# GPSModule.net
KiCad netlist of a schematic drawn in Altium Designer
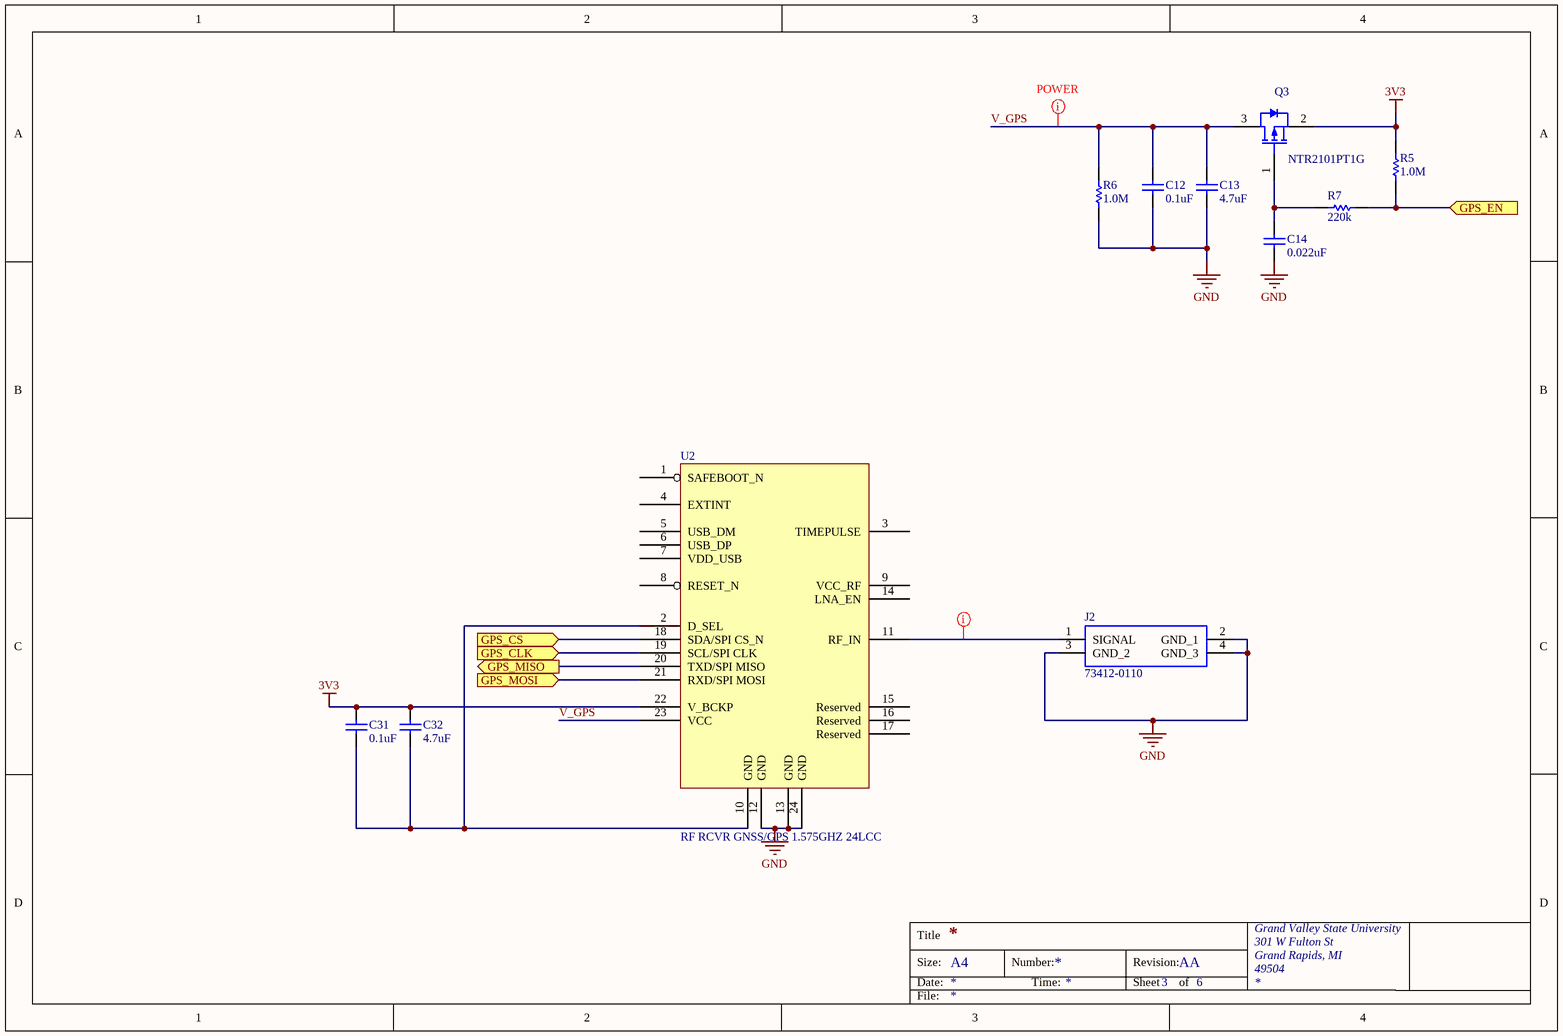
[diagram p0: GPSModule.SchDoc]

(export (version "E")
  (design (tool "Eeschema 10.0.6"))
  (components
    (comp (ref "C12")
      (value "0.1uF")
      (footprint "0402cap")
      (description "0402 Ceramic Chip Capacitor - Standard")
      (fields (field (name "Comment") "C0402"))
      (libsource (lib "lib-Standard") (part "C0402"))
    )
    (comp (ref "C13")
      (value "4.7uF")
      (footprint "0603CAP")
      (description "0603 Ceramic Chip Capacitor - Standard")
      (fields (field (name "Comment") "C0603"))
      (libsource (lib "lib-Standard") (part "C0603"))
    )
    (comp (ref "C14")
      (value "0.022uF")
      (footprint "0402cap")
      (description "0402 Ceramic Chip Capacitor - Standard")
      (fields (field (name "Comment") "C0402"))
      (libsource (lib "lib-Standard") (part "C0402"))
    )
    (comp (ref "C31")
      (value "0.1uF")
      (footprint "0402cap")
      (description "0402 Ceramic Chip Capacitor - Standard")
      (fields (field (name "Comment") "C0402"))
      (libsource (lib "lib-Standard") (part "C0402"))
    )
    (comp (ref "C32")
      (value "4.7uF")
      (footprint "0603CAP")
      (description "0603 Ceramic Chip Capacitor - Standard")
      (fields (field (name "Comment") "C0603"))
      (libsource (lib "lib-Standard") (part "C0603"))
    )
    (comp (ref "J2")
      (value "73412-0110")
      (footprint "73412-0110")
      (description "50 Ohms, MCRF, PCB Vertical Jack Receptacle, SMT, 1.25mm Mounted Height")
      (fields (field (name "RS PART NUMBER") "1676350") (field (name "MOUSER PART NUMBER") "538-73412-0110"))
      (libsource (lib "lib-Connectors") (part "73412-0110"))
    )
    (comp (ref "Q3")
      (value "NTR2101PT1G")
      (footprint "ONSC-SOT-23-3-318-08_V")
      (description "Small Signal MOSFET, -8 V, -3.7 A, Single P-Channel, 3-Pin SOT-23, Pb-Free, Tape and Reel")
      (libsource (lib "ON Semi MOSFETs") (part "NTR2101PT1G"))
    )
    (comp (ref "R5")
      (value "1.0M")
      (footprint "0402RES")
      (description "0402 Chip Resistor - Standard")
      (fields (field (name "Comment") "R0402"))
      (libsource (lib "lib-Standard") (part "R0402"))
    )
    (comp (ref "R6")
      (value "1.0M")
      (footprint "0402RES")
      (description "0402 Chip Resistor - Standard")
      (fields (field (name "Comment") "R0402"))
      (libsource (lib "lib-Standard") (part "R0402"))
    )
    (comp (ref "R7")
      (value "220k")
      (footprint "0402RES")
      (description "0402 Chip Resistor - Standard")
      (fields (field (name "Comment") "R0402"))
      (libsource (lib "lib-Standard") (part "R0402"))
    )
    (comp (ref "U2")
      (value "RF RCVR GNSS/GPS 1.575GHZ 24LCC")
      (footprint "NEO-M8N-0")
      (description "Concurrent GNSS LCC module, TCXO, Flash, SAW, LNA")
      (libsource (lib "lib-IC_RF") (part "NEO-M8N-0"))
    )
  )
  (nets
    (net (code "1") (name "/GPS_CLK") (class "Default")
      (node (ref "U2") (pin "19") (pinfunction "SCL/SPI_CLK_19") (pintype "passive"))
    )
    (net (code "2") (name "/GPS_CS") (class "Default")
      (node (ref "U2") (pin "18") (pinfunction "SDA/SPI_CS_N_18") (pintype "passive"))
    )
    (net (code "3") (name "/GPS_EN") (class "Default")
      (node (ref "R5") (pin "1") (pinfunction "1_1") (pintype "passive"))
      (node (ref "R7") (pin "1") (pinfunction "1_1") (pintype "passive"))
    )
    (net (code "4") (name "/GPS_MISO") (class "Default")
      (node (ref "U2") (pin "20") (pinfunction "TXD/SPI_MISO_20") (pintype "passive"))
    )
    (net (code "5") (name "/GPS_MOSI") (class "Default")
      (node (ref "U2") (pin "21") (pinfunction "RXD/SPI_MOSI_21") (pintype "passive"))
    )
    (net (code "6") (name "/V_GPS") (class "Default")
      (node (ref "C12") (pin "2") (pinfunction "2_2") (pintype "passive"))
      (node (ref "C13") (pin "2") (pinfunction "2_2") (pintype "passive"))
      (node (ref "Q3") (pin "3") (pinfunction "D_3") (pintype "passive"))
      (node (ref "R6") (pin "2") (pinfunction "2_2") (pintype "passive"))
      (node (ref "U2") (pin "23") (pinfunction "VCC_23") (pintype "passive"))
    )
    (net (code "7") (name "3V3") (class "Default")
      (node (ref "C31") (pin "2") (pinfunction "2_2") (pintype "passive"))
      (node (ref "C32") (pin "2") (pinfunction "2_2") (pintype "passive"))
      (node (ref "Q3") (pin "2") (pinfunction "S_2") (pintype "passive"))
      (node (ref "R5") (pin "2") (pinfunction "2_2") (pintype "passive"))
      (node (ref "U2") (pin "22") (pinfunction "V_BCKP_22") (pintype "passive"))
    )
    (net (code "8") (name "GND") (class "Default")
      (node (ref "C12") (pin "1") (pinfunction "1_1") (pintype "passive"))
      (node (ref "C13") (pin "1") (pinfunction "1_1") (pintype "passive"))
      (node (ref "C14") (pin "1") (pinfunction "1_1") (pintype "passive"))
      (node (ref "J2") (pin "2") (pinfunction "GND_1_2") (pintype "passive"))
      (node (ref "J2") (pin "3") (pinfunction "GND_2_3") (pintype "passive"))
      (node (ref "J2") (pin "4") (pinfunction "GND_3_4") (pintype "passive"))
      (node (ref "R6") (pin "1") (pinfunction "1_1") (pintype "passive"))
      (node (ref "U2") (pin "12") (pinfunction "GND_12") (pintype "passive"))
      (node (ref "U2") (pin "13") (pinfunction "GND_13") (pintype "passive"))
      (node (ref "U2") (pin "24") (pinfunction "GND_24") (pintype "passive"))
    )
    (net (code "9") (name "Net-(J2-SIGNAL)") (class "Default")
      (node (ref "J2") (pin "1") (pinfunction "SIGNAL_1") (pintype "passive"))
      (node (ref "U2") (pin "11") (pinfunction "RF_IN_11") (pintype "passive"))
    )
    (net (code "10") (name "Net-(Q3-G)") (class "Default")
      (node (ref "C14") (pin "2") (pinfunction "2_2") (pintype "passive"))
      (node (ref "Q3") (pin "1") (pinfunction "G_1") (pintype "passive"))
      (node (ref "R7") (pin "2") (pinfunction "2_2") (pintype "passive"))
    )
    (net (code "11") (name "Net-(U2-D_SEL)") (class "Default")
      (node (ref "C31") (pin "1") (pinfunction "1_1") (pintype "passive"))
      (node (ref "C32") (pin "1") (pinfunction "1_1") (pintype "passive"))
      (node (ref "U2") (pin "10") (pinfunction "GND_10") (pintype "passive"))
      (node (ref "U2") (pin "2") (pinfunction "D_SEL_2") (pintype "passive"))
    )
    (net (code "12") (name "unconnected-(U2-EXTINT-Pad4)") (class "Default")
      (node (ref "U2") (pin "4") (pinfunction "EXTINT_4") (pintype "passive"))
    )
    (net (code "13") (name "unconnected-(U2-LNA_EN-Pad14)") (class "Default")
      (node (ref "U2") (pin "14") (pinfunction "LNA_EN_14") (pintype "passive"))
    )
    (net (code "14") (name "unconnected-(U2-RESET_N-Pad8)") (class "Default")
      (node (ref "U2") (pin "8") (pinfunction "RESET_N_8") (pintype "passive"))
    )
    (net (code "15") (name "unconnected-(U2-Reserved-Pad15)") (class "Default")
      (node (ref "U2") (pin "15") (pinfunction "Reserved_15") (pintype "passive"))
    )
    (net (code "16") (name "unconnected-(U2-Reserved-Pad16)") (class "Default")
      (node (ref "U2") (pin "16") (pinfunction "Reserved_16") (pintype "passive"))
    )
    (net (code "17") (name "unconnected-(U2-Reserved-Pad17)") (class "Default")
      (node (ref "U2") (pin "17") (pinfunction "Reserved_17") (pintype "passive"))
    )
    (net (code "18") (name "unconnected-(U2-SAFEBOOT_N-Pad1)") (class "Default")
      (node (ref "U2") (pin "1") (pinfunction "SAFEBOOT_N_1") (pintype "passive"))
    )
    (net (code "19") (name "unconnected-(U2-TIMEPULSE-Pad3)") (class "Default")
      (node (ref "U2") (pin "3") (pinfunction "TIMEPULSE_3") (pintype "passive"))
    )
    (net (code "20") (name "unconnected-(U2-USB_DM-Pad5)") (class "Default")
      (node (ref "U2") (pin "5") (pinfunction "USB_DM_5") (pintype "passive"))
    )
    (net (code "21") (name "unconnected-(U2-USB_DP-Pad6)") (class "Default")
      (node (ref "U2") (pin "6") (pinfunction "USB_DP_6") (pintype "passive"))
    )
    (net (code "22") (name "unconnected-(U2-VCC_RF-Pad9)") (class "Default")
      (node (ref "U2") (pin "9") (pinfunction "VCC_RF_9") (pintype "passive"))
    )
    (net (code "23") (name "unconnected-(U2-VDD_USB-Pad7)") (class "Default")
      (node (ref "U2") (pin "7") (pinfunction "VDD_USB_7") (pintype "passive"))
    )
  )
)
